# W25Q128.net
KiCad netlist of a schematic drawn in Altium Designer
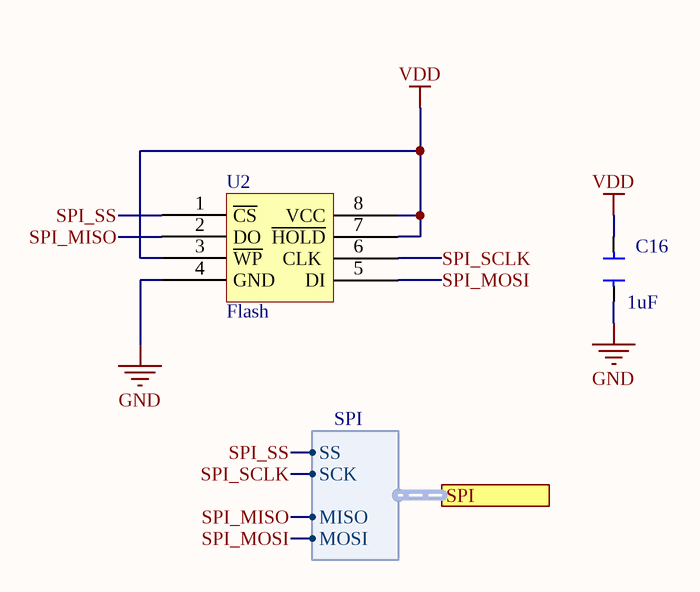
[diagram p0: W25Q128.SchDoc]

(export (version "E")
  (design (tool "Eeschema 10.0.6"))
  (components
    (comp (ref "C16")
      (value "1uF")
      (footprint "Cap_0603")
      (fields (field (name "Comment") "Cap"))
      (libsource (lib "ZGR") (part "Cap"))
    )
    (comp (ref "U2") (value "Flash") (footprint "8-Pin SOIC 208-mil") (libsource (lib "ZGR") (part "W25QXX")))
  )
  (nets
    (net (code "2") (name "/SPI_MISO") (class "Default")
      (node (ref "U2") (pin "2") (pinfunction "DO_2") (pintype "passive"))
    )
    (net (code "3") (name "/SPI_MOSI") (class "Default")
      (node (ref "U2") (pin "5") (pinfunction "DI_5") (pintype "passive"))
    )
    (net (code "4") (name "/SPI_SCLK") (class "Default")
      (node (ref "U2") (pin "6") (pinfunction "CLK_6") (pintype "passive"))
    )
    (net (code "5") (name "/SPI_SS") (class "Default")
      (node (ref "U2") (pin "1") (pinfunction "~{CS}_1") (pintype "passive"))
    )
    (net (code "7") (name "GND") (class "Default")
      (node (ref "C16") (pin "2") (pinfunction "2_2") (pintype "passive"))
      (node (ref "U2") (pin "4") (pinfunction "GND_4") (pintype "passive"))
    )
    (net (code "8") (name "VDD") (class "Default")
      (node (ref "C16") (pin "1") (pinfunction "1_1") (pintype "passive"))
      (node (ref "U2") (pin "3") (pinfunction "~{WP}_3") (pintype "passive"))
      (node (ref "U2") (pin "7") (pinfunction "~{HOLD}_7") (pintype "passive"))
      (node (ref "U2") (pin "8") (pinfunction "VCC_8") (pintype "passive"))
    )
  )
)
